# amplifier.net
KiCad netlist of a schematic drawn in EAGLE
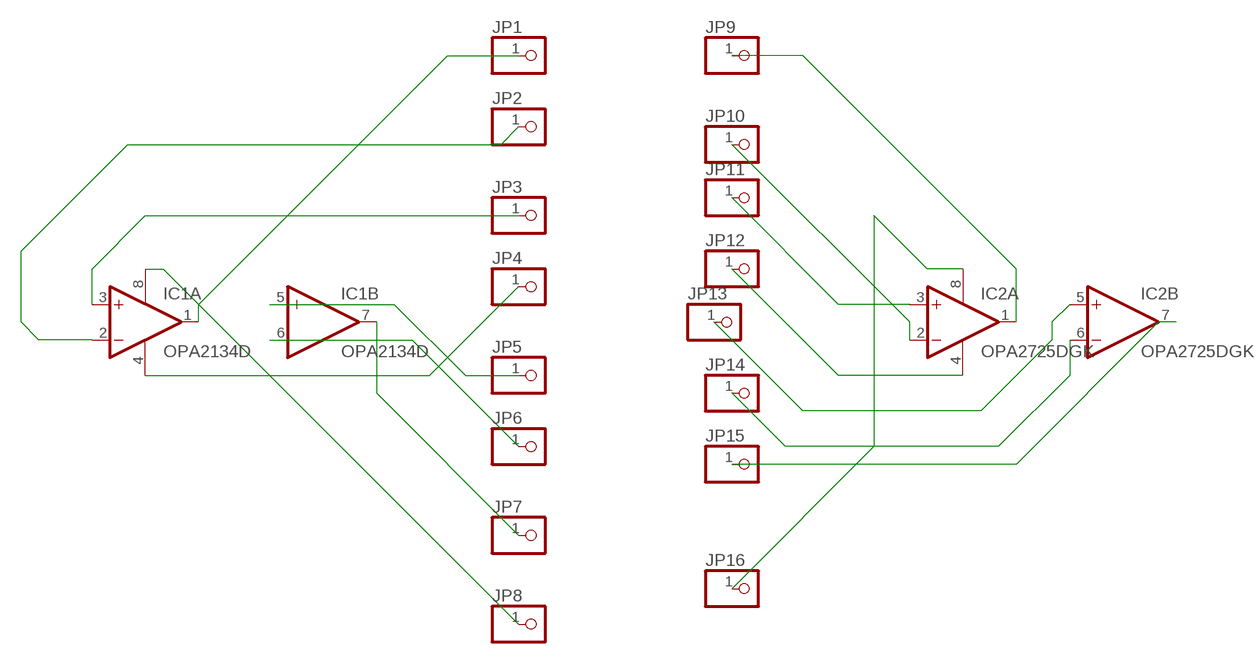
[diagram p0: schematic, sheet 1]

(export (version "E")
  (design (tool "Eeschema 10.0.6"))
  (components
    (comp (ref "IC1")
      (value "OPA2134D")
      (footprint "eagle-import:SOIC8")
      (libsource (lib "eagle-import") (part "OPA2134D"))
    )
    (comp (ref "IC2")
      (value "OPA2725DGK")
      (footprint "eagle-import:MSOP08")
      (libsource (lib "eagle-import") (part "OPA2725DGK"))
    )
    (comp (ref "JP1")
      (value "PINHD-1X1")
      (footprint "eagle-import:1X01")
      (libsource (lib "eagle-import") (part "PINHD-1X1"))
    )
    (comp (ref "JP2")
      (value "PINHD-1X1")
      (footprint "eagle-import:1X01")
      (libsource (lib "eagle-import") (part "PINHD-1X1"))
    )
    (comp (ref "JP3")
      (value "PINHD-1X1")
      (footprint "eagle-import:1X01")
      (libsource (lib "eagle-import") (part "PINHD-1X1"))
    )
    (comp (ref "JP4")
      (value "PINHD-1X1")
      (footprint "eagle-import:1X01")
      (libsource (lib "eagle-import") (part "PINHD-1X1"))
    )
    (comp (ref "JP5")
      (value "PINHD-1X1")
      (footprint "eagle-import:1X01")
      (libsource (lib "eagle-import") (part "PINHD-1X1"))
    )
    (comp (ref "JP6")
      (value "PINHD-1X1")
      (footprint "eagle-import:1X01")
      (libsource (lib "eagle-import") (part "PINHD-1X1"))
    )
    (comp (ref "JP7")
      (value "PINHD-1X1")
      (footprint "eagle-import:1X01")
      (libsource (lib "eagle-import") (part "PINHD-1X1"))
    )
    (comp (ref "JP8")
      (value "PINHD-1X1")
      (footprint "eagle-import:1X01")
      (libsource (lib "eagle-import") (part "PINHD-1X1"))
    )
    (comp (ref "JP9")
      (value "PINHD-1X1")
      (footprint "eagle-import:1X01")
      (libsource (lib "eagle-import") (part "PINHD-1X1"))
    )
    (comp (ref "JP10")
      (value "PINHD-1X1")
      (footprint "eagle-import:1X01")
      (libsource (lib "eagle-import") (part "PINHD-1X1"))
    )
    (comp (ref "JP11")
      (value "PINHD-1X1")
      (footprint "eagle-import:1X01")
      (libsource (lib "eagle-import") (part "PINHD-1X1"))
    )
    (comp (ref "JP12")
      (value "PINHD-1X1")
      (footprint "eagle-import:1X01")
      (libsource (lib "eagle-import") (part "PINHD-1X1"))
    )
    (comp (ref "JP13")
      (value "PINHD-1X1")
      (footprint "eagle-import:1X01")
      (libsource (lib "eagle-import") (part "PINHD-1X1"))
    )
    (comp (ref "JP14")
      (value "PINHD-1X1")
      (footprint "eagle-import:1X01")
      (libsource (lib "eagle-import") (part "PINHD-1X1"))
    )
    (comp (ref "JP15")
      (value "PINHD-1X1")
      (footprint "eagle-import:1X01")
      (libsource (lib "eagle-import") (part "PINHD-1X1"))
    )
    (comp (ref "JP16")
      (value "PINHD-1X1")
      (footprint "eagle-import:1X01")
      (libsource (lib "eagle-import") (part "PINHD-1X1"))
    )
  )
  (nets
    (net (code "1") (name "Net-(IC1A-+IN)") (class "Default")
      (node (ref "IC1") (pin "3") (pinfunction "+IN_3") (pintype "input"))
      (node (ref "JP3") (pin "1") (pinfunction "1_1") (pintype "passive"))
    )
    (net (code "2") (name "Net-(IC1A--IN)") (class "Default")
      (node (ref "IC1") (pin "2") (pinfunction "-IN_2") (pintype "input"))
      (node (ref "JP2") (pin "1") (pinfunction "1_1") (pintype "passive"))
    )
    (net (code "3") (name "Net-(IC1A-OUT)") (class "Default")
      (node (ref "IC1") (pin "1") (pinfunction "OUT_1") (pintype "output"))
      (node (ref "JP1") (pin "1") (pinfunction "1_1") (pintype "passive"))
    )
    (net (code "4") (name "Net-(IC1B-+IN)") (class "Default")
      (node (ref "IC1") (pin "5") (pinfunction "+IN_5") (pintype "input"))
      (node (ref "JP5") (pin "1") (pinfunction "1_1") (pintype "passive"))
    )
    (net (code "5") (name "Net-(IC1B--IN)") (class "Default")
      (node (ref "IC1") (pin "6") (pinfunction "-IN_6") (pintype "input"))
      (node (ref "JP6") (pin "1") (pinfunction "1_1") (pintype "passive"))
    )
    (net (code "6") (name "Net-(IC1B-OUT)") (class "Default")
      (node (ref "IC1") (pin "7") (pinfunction "OUT_7") (pintype "output"))
      (node (ref "JP7") (pin "1") (pinfunction "1_1") (pintype "passive"))
    )
    (net (code "7") (name "Net-(IC1C-V+)") (class "Default")
      (node (ref "IC1") (pin "8") (pinfunction "V+_8") (pintype "power_in"))
      (node (ref "JP8") (pin "1") (pinfunction "1_1") (pintype "passive"))
    )
    (net (code "8") (name "Net-(IC1C-V-)") (class "Default")
      (node (ref "IC1") (pin "4") (pinfunction "V-_4") (pintype "power_in"))
      (node (ref "JP4") (pin "1") (pinfunction "1_1") (pintype "passive"))
    )
    (net (code "9") (name "Net-(IC2A-+IN)") (class "Default")
      (node (ref "IC2") (pin "3") (pinfunction "+IN_3") (pintype "input"))
      (node (ref "JP11") (pin "1") (pinfunction "1_1") (pintype "passive"))
    )
    (net (code "10") (name "Net-(IC2A--IN)") (class "Default")
      (node (ref "IC2") (pin "2") (pinfunction "-IN_2") (pintype "input"))
      (node (ref "JP10") (pin "1") (pinfunction "1_1") (pintype "passive"))
    )
    (net (code "11") (name "Net-(IC2A-OUT)") (class "Default")
      (node (ref "IC2") (pin "1") (pinfunction "OUT_1") (pintype "output"))
      (node (ref "JP9") (pin "1") (pinfunction "1_1") (pintype "passive"))
    )
    (net (code "12") (name "Net-(IC2B-+IN)") (class "Default")
      (node (ref "IC2") (pin "5") (pinfunction "+IN_5") (pintype "input"))
      (node (ref "JP13") (pin "1") (pinfunction "1_1") (pintype "passive"))
    )
    (net (code "13") (name "Net-(IC2B--IN)") (class "Default")
      (node (ref "IC2") (pin "6") (pinfunction "-IN_6") (pintype "input"))
      (node (ref "JP14") (pin "1") (pinfunction "1_1") (pintype "passive"))
    )
    (net (code "14") (name "Net-(IC2B-OUT)") (class "Default")
      (node (ref "IC2") (pin "7") (pinfunction "OUT_7") (pintype "output"))
      (node (ref "JP15") (pin "1") (pinfunction "1_1") (pintype "passive"))
    )
    (net (code "15") (name "Net-(IC2C-V+)") (class "Default")
      (node (ref "IC2") (pin "8") (pinfunction "V+_8") (pintype "power_in"))
      (node (ref "JP16") (pin "1") (pinfunction "1_1") (pintype "passive"))
    )
    (net (code "16") (name "Net-(IC2C-V-)") (class "Default")
      (node (ref "IC2") (pin "4") (pinfunction "V-_4") (pintype "power_in"))
      (node (ref "JP12") (pin "1") (pinfunction "1_1") (pintype "passive"))
    )
  )
)
